# matrix_led_shield_schematic.net
KiCad netlist of a schematic drawn in EAGLE
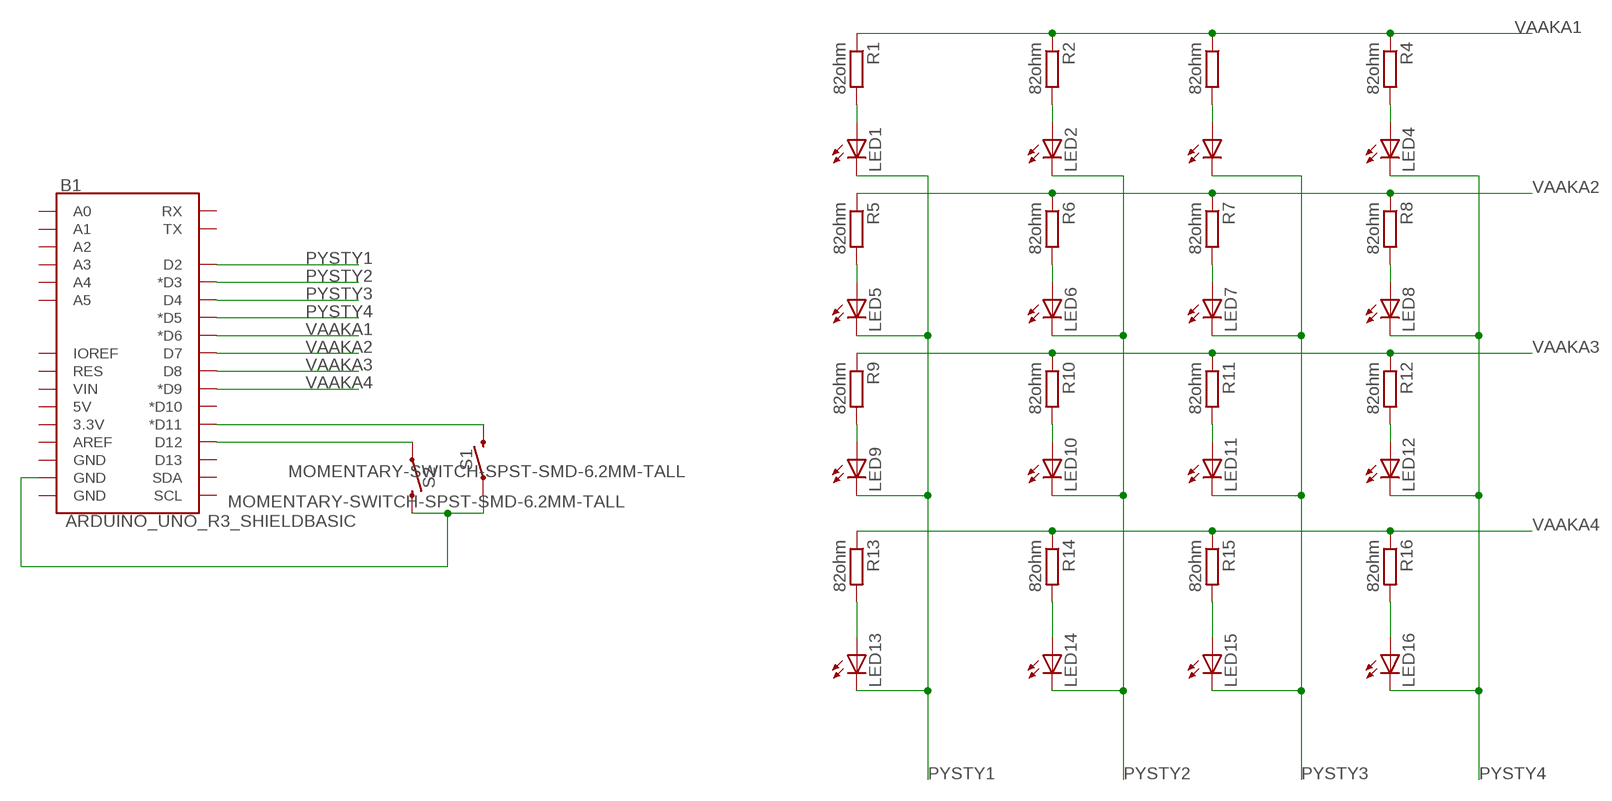
[diagram p0: schematic, sheet 1]

(export (version "E")
  (design (tool "Eeschema 10.0.6"))
  (components
    (comp (ref "B1")
      (value "ARDUINO_UNO_R3_SHIELDBASIC")
      (footprint "eagle-import:UNO_R3_SHIELD")
      (libsource (lib "eagle-import") (part "ARDUINO_UNO_R3_SHIELDBASIC"))
    )
    (comp (ref "LED1")
      (value "LG_T679-E1F1-1")
      (footprint "eagle-import:PLCC2")
      (libsource (lib "eagle-import") (part "_T679-?-1E1F1LG"))
    )
    (comp (ref "LED2")
      (value "LG_T679-E1F1-1")
      (footprint "eagle-import:PLCC2")
      (libsource (lib "eagle-import") (part "_T679-?-1E1F1LG"))
    )
    (comp (ref "LED3")
      (value "LG_T679-E1F1-1")
      (footprint "eagle-import:PLCC2")
      (libsource (lib "eagle-import") (part "_T679-?-1E1F1LG"))
    )
    (comp (ref "LED4")
      (value "LG_T679-E1F1-1")
      (footprint "eagle-import:PLCC2")
      (libsource (lib "eagle-import") (part "_T679-?-1E1F1LG"))
    )
    (comp (ref "LED5")
      (value "LG_T679-E1F1-1")
      (footprint "eagle-import:PLCC2")
      (libsource (lib "eagle-import") (part "_T679-?-1E1F1LG"))
    )
    (comp (ref "LED6")
      (value "LG_T679-E1F1-1")
      (footprint "eagle-import:PLCC2")
      (libsource (lib "eagle-import") (part "_T679-?-1E1F1LG"))
    )
    (comp (ref "LED7")
      (value "LG_T679-E1F1-1")
      (footprint "eagle-import:PLCC2")
      (libsource (lib "eagle-import") (part "_T679-?-1E1F1LG"))
    )
    (comp (ref "LED8")
      (value "LG_T679-E1F1-1")
      (footprint "eagle-import:PLCC2")
      (libsource (lib "eagle-import") (part "_T679-?-1E1F1LG"))
    )
    (comp (ref "LED9")
      (value "LG_T679-E1F1-1")
      (footprint "eagle-import:PLCC2")
      (libsource (lib "eagle-import") (part "_T679-?-1E1F1LG"))
    )
    (comp (ref "LED10")
      (value "LG_T679-E1F1-1")
      (footprint "eagle-import:PLCC2")
      (libsource (lib "eagle-import") (part "_T679-?-1E1F1LG"))
    )
    (comp (ref "LED11")
      (value "LG_T679-E1F1-1")
      (footprint "eagle-import:PLCC2")
      (libsource (lib "eagle-import") (part "_T679-?-1E1F1LG"))
    )
    (comp (ref "LED12")
      (value "LG_T679-E1F1-1")
      (footprint "eagle-import:PLCC2")
      (libsource (lib "eagle-import") (part "_T679-?-1E1F1LG"))
    )
    (comp (ref "LED13")
      (value "LG_T679-E1F1-1")
      (footprint "eagle-import:PLCC2")
      (libsource (lib "eagle-import") (part "_T679-?-1E1F1LG"))
    )
    (comp (ref "LED14")
      (value "LG_T679-E1F1-1")
      (footprint "eagle-import:PLCC2")
      (libsource (lib "eagle-import") (part "_T679-?-1E1F1LG"))
    )
    (comp (ref "LED15")
      (value "LG_T679-E1F1-1")
      (footprint "eagle-import:PLCC2")
      (libsource (lib "eagle-import") (part "_T679-?-1E1F1LG"))
    )
    (comp (ref "LED16")
      (value "LG_T679-E1F1-1")
      (footprint "eagle-import:PLCC2")
      (libsource (lib "eagle-import") (part "_T679-?-1E1F1LG"))
    )
    (comp (ref "R1")
      (value "82ohm")
      (footprint "eagle-import:M0805")
      (libsource (lib "eagle-import") (part "R-EU_M0805"))
    )
    (comp (ref "R2")
      (value "82ohm")
      (footprint "eagle-import:M0805")
      (libsource (lib "eagle-import") (part "R-EU_M0805"))
    )
    (comp (ref "R3")
      (value "82ohm")
      (footprint "eagle-import:M0805")
      (libsource (lib "eagle-import") (part "R-EU_M0805"))
    )
    (comp (ref "R4")
      (value "82ohm")
      (footprint "eagle-import:M0805")
      (libsource (lib "eagle-import") (part "R-EU_M0805"))
    )
    (comp (ref "R5")
      (value "82ohm")
      (footprint "eagle-import:M0805")
      (libsource (lib "eagle-import") (part "R-EU_M0805"))
    )
    (comp (ref "R6")
      (value "82ohm")
      (footprint "eagle-import:M0805")
      (libsource (lib "eagle-import") (part "R-EU_M0805"))
    )
    (comp (ref "R7")
      (value "82ohm")
      (footprint "eagle-import:M0805")
      (libsource (lib "eagle-import") (part "R-EU_M0805"))
    )
    (comp (ref "R8")
      (value "82ohm")
      (footprint "eagle-import:M0805")
      (libsource (lib "eagle-import") (part "R-EU_M0805"))
    )
    (comp (ref "R9")
      (value "82ohm")
      (footprint "eagle-import:M0805")
      (libsource (lib "eagle-import") (part "R-EU_M0805"))
    )
    (comp (ref "R10")
      (value "82ohm")
      (footprint "eagle-import:M0805")
      (libsource (lib "eagle-import") (part "R-EU_M0805"))
    )
    (comp (ref "R11")
      (value "82ohm")
      (footprint "eagle-import:M0805")
      (libsource (lib "eagle-import") (part "R-EU_M0805"))
    )
    (comp (ref "R12")
      (value "82ohm")
      (footprint "eagle-import:M0805")
      (libsource (lib "eagle-import") (part "R-EU_M0805"))
    )
    (comp (ref "R13")
      (value "82ohm")
      (footprint "eagle-import:M0805")
      (libsource (lib "eagle-import") (part "R-EU_M0805"))
    )
    (comp (ref "R14")
      (value "82ohm")
      (footprint "eagle-import:M0805")
      (libsource (lib "eagle-import") (part "R-EU_M0805"))
    )
    (comp (ref "R15")
      (value "82ohm")
      (footprint "eagle-import:M0805")
      (libsource (lib "eagle-import") (part "R-EU_M0805"))
    )
    (comp (ref "R16")
      (value "82ohm")
      (footprint "eagle-import:M0805")
      (libsource (lib "eagle-import") (part "R-EU_M0805"))
    )
    (comp (ref "S1")
      (value "MOMENTARY-SWITCH-SPST-SMD-6.2MM-TALL")
      (footprint "eagle-import:TACTILE_SWITCH_SMD_6.2MM_TALL")
      (libsource (lib "eagle-import") (part "MOMENTARY-SWITCH-SPST-SMD-6.2MM-TALL"))
    )
    (comp (ref "S2")
      (value "MOMENTARY-SWITCH-SPST-SMD-6.2MM-TALL")
      (footprint "eagle-import:TACTILE_SWITCH_SMD_6.2MM_TALL")
      (libsource (lib "eagle-import") (part "MOMENTARY-SWITCH-SPST-SMD-6.2MM-TALL"))
    )
  )
  (nets
    (net (code "1") (name "/PYSTY1") (class "Default")
      (node (ref "B1") (pin "D2") (pinfunction "D2_D2") (pintype "bidirectional"))
      (node (ref "LED1") (pin "C") (pinfunction "C_C") (pintype "passive"))
      (node (ref "LED13") (pin "C") (pinfunction "C_C") (pintype "passive"))
      (node (ref "LED5") (pin "C") (pinfunction "C_C") (pintype "passive"))
      (node (ref "LED9") (pin "C") (pinfunction "C_C") (pintype "passive"))
    )
    (net (code "2") (name "/PYSTY2") (class "Default")
      (node (ref "B1") (pin "D3") (pinfunction "*D3_D3") (pintype "bidirectional"))
      (node (ref "LED10") (pin "C") (pinfunction "C_C") (pintype "passive"))
      (node (ref "LED14") (pin "C") (pinfunction "C_C") (pintype "passive"))
      (node (ref "LED2") (pin "C") (pinfunction "C_C") (pintype "passive"))
      (node (ref "LED6") (pin "C") (pinfunction "C_C") (pintype "passive"))
    )
    (net (code "3") (name "/PYSTY3") (class "Default")
      (node (ref "B1") (pin "D4") (pinfunction "D4_D4") (pintype "bidirectional"))
      (node (ref "LED11") (pin "C") (pinfunction "C_C") (pintype "passive"))
      (node (ref "LED15") (pin "C") (pinfunction "C_C") (pintype "passive"))
      (node (ref "LED3") (pin "C") (pinfunction "C_C") (pintype "passive"))
      (node (ref "LED7") (pin "C") (pinfunction "C_C") (pintype "passive"))
    )
    (net (code "4") (name "/PYSTY4") (class "Default")
      (node (ref "B1") (pin "D5") (pinfunction "*D5_D5") (pintype "bidirectional"))
      (node (ref "LED12") (pin "C") (pinfunction "C_C") (pintype "passive"))
      (node (ref "LED16") (pin "C") (pinfunction "C_C") (pintype "passive"))
      (node (ref "LED4") (pin "C") (pinfunction "C_C") (pintype "passive"))
      (node (ref "LED8") (pin "C") (pinfunction "C_C") (pintype "passive"))
    )
    (net (code "5") (name "/VAAKA1") (class "Default")
      (node (ref "B1") (pin "D6") (pinfunction "*D6_D6") (pintype "bidirectional"))
      (node (ref "R1") (pin "1") (pinfunction "1_1") (pintype "passive"))
      (node (ref "R2") (pin "1") (pinfunction "1_1") (pintype "passive"))
      (node (ref "R3") (pin "1") (pinfunction "1_1") (pintype "passive"))
      (node (ref "R4") (pin "1") (pinfunction "1_1") (pintype "passive"))
    )
    (net (code "6") (name "/VAAKA2") (class "Default")
      (node (ref "B1") (pin "D7") (pinfunction "D7_D7") (pintype "bidirectional"))
      (node (ref "R5") (pin "1") (pinfunction "1_1") (pintype "passive"))
      (node (ref "R6") (pin "1") (pinfunction "1_1") (pintype "passive"))
      (node (ref "R7") (pin "1") (pinfunction "1_1") (pintype "passive"))
      (node (ref "R8") (pin "1") (pinfunction "1_1") (pintype "passive"))
    )
    (net (code "7") (name "/VAAKA3") (class "Default")
      (node (ref "B1") (pin "D8") (pinfunction "D8_D8") (pintype "bidirectional"))
      (node (ref "R10") (pin "1") (pinfunction "1_1") (pintype "passive"))
      (node (ref "R11") (pin "1") (pinfunction "1_1") (pintype "passive"))
      (node (ref "R12") (pin "1") (pinfunction "1_1") (pintype "passive"))
      (node (ref "R9") (pin "1") (pinfunction "1_1") (pintype "passive"))
    )
    (net (code "8") (name "/VAAKA4") (class "Default")
      (node (ref "B1") (pin "D9") (pinfunction "*D9_D9") (pintype "bidirectional"))
      (node (ref "R13") (pin "1") (pinfunction "1_1") (pintype "passive"))
      (node (ref "R14") (pin "1") (pinfunction "1_1") (pintype "passive"))
      (node (ref "R15") (pin "1") (pinfunction "1_1") (pintype "passive"))
      (node (ref "R16") (pin "1") (pinfunction "1_1") (pintype "passive"))
    )
    (net (code "9") (name "Net-(B1-*D11)") (class "Default")
      (node (ref "B1") (pin "D11") (pinfunction "*D11_D11") (pintype "bidirectional"))
      (node (ref "S1") (pin "B2") (pinfunction "2_B2") (pintype "passive"))
    )
    (net (code "10") (name "Net-(LED1-PadA)") (class "Default")
      (node (ref "LED1") (pin "A") (pinfunction "A_A") (pintype "passive"))
      (node (ref "R1") (pin "2") (pinfunction "2_2") (pintype "passive"))
    )
    (net (code "11") (name "Net-(LED2-PadA)") (class "Default")
      (node (ref "LED2") (pin "A") (pinfunction "A_A") (pintype "passive"))
      (node (ref "R2") (pin "2") (pinfunction "2_2") (pintype "passive"))
    )
    (net (code "12") (name "Net-(LED3-PadA)") (class "Default")
      (node (ref "LED3") (pin "A") (pinfunction "A_A") (pintype "passive"))
      (node (ref "R3") (pin "2") (pinfunction "2_2") (pintype "passive"))
    )
    (net (code "13") (name "Net-(LED4-PadA)") (class "Default")
      (node (ref "LED4") (pin "A") (pinfunction "A_A") (pintype "passive"))
      (node (ref "R4") (pin "2") (pinfunction "2_2") (pintype "passive"))
    )
    (net (code "14") (name "Net-(LED5-PadA)") (class "Default")
      (node (ref "LED5") (pin "A") (pinfunction "A_A") (pintype "passive"))
      (node (ref "R5") (pin "2") (pinfunction "2_2") (pintype "passive"))
    )
    (net (code "15") (name "Net-(LED6-PadA)") (class "Default")
      (node (ref "LED6") (pin "A") (pinfunction "A_A") (pintype "passive"))
      (node (ref "R6") (pin "2") (pinfunction "2_2") (pintype "passive"))
    )
    (net (code "16") (name "Net-(LED7-PadA)") (class "Default")
      (node (ref "LED7") (pin "A") (pinfunction "A_A") (pintype "passive"))
      (node (ref "R7") (pin "2") (pinfunction "2_2") (pintype "passive"))
    )
    (net (code "17") (name "Net-(LED8-PadA)") (class "Default")
      (node (ref "LED8") (pin "A") (pinfunction "A_A") (pintype "passive"))
      (node (ref "R8") (pin "2") (pinfunction "2_2") (pintype "passive"))
    )
    (net (code "18") (name "Net-(LED9-PadA)") (class "Default")
      (node (ref "LED9") (pin "A") (pinfunction "A_A") (pintype "passive"))
      (node (ref "R9") (pin "2") (pinfunction "2_2") (pintype "passive"))
    )
    (net (code "19") (name "Net-(LED10-PadA)") (class "Default")
      (node (ref "LED10") (pin "A") (pinfunction "A_A") (pintype "passive"))
      (node (ref "R10") (pin "2") (pinfunction "2_2") (pintype "passive"))
    )
    (net (code "20") (name "Net-(LED11-PadA)") (class "Default")
      (node (ref "LED11") (pin "A") (pinfunction "A_A") (pintype "passive"))
      (node (ref "R11") (pin "2") (pinfunction "2_2") (pintype "passive"))
    )
    (net (code "21") (name "Net-(LED12-PadA)") (class "Default")
      (node (ref "LED12") (pin "A") (pinfunction "A_A") (pintype "passive"))
      (node (ref "R12") (pin "2") (pinfunction "2_2") (pintype "passive"))
    )
    (net (code "22") (name "Net-(LED13-PadA)") (class "Default")
      (node (ref "LED13") (pin "A") (pinfunction "A_A") (pintype "passive"))
      (node (ref "R13") (pin "2") (pinfunction "2_2") (pintype "passive"))
    )
    (net (code "23") (name "Net-(LED14-PadA)") (class "Default")
      (node (ref "LED14") (pin "A") (pinfunction "A_A") (pintype "passive"))
      (node (ref "R14") (pin "2") (pinfunction "2_2") (pintype "passive"))
    )
    (net (code "24") (name "Net-(LED15-PadA)") (class "Default")
      (node (ref "LED15") (pin "A") (pinfunction "A_A") (pintype "passive"))
      (node (ref "R15") (pin "2") (pinfunction "2_2") (pintype "passive"))
    )
    (net (code "25") (name "Net-(LED16-PadA)") (class "Default")
      (node (ref "LED16") (pin "A") (pinfunction "A_A") (pintype "passive"))
      (node (ref "R16") (pin "2") (pinfunction "2_2") (pintype "passive"))
    )
    (net (code "26") (name "Net-(S1-1)") (class "Default")
      (node (ref "B1") (pin "GND@1") (pinfunction "GND_GND@1") (pintype "bidirectional"))
      (node (ref "S1") (pin "A2") (pinfunction "1_A2") (pintype "passive"))
      (node (ref "S2") (pin "B2") (pinfunction "2_B2") (pintype "passive"))
    )
    (net (code "27") (name "Net-(S2-1)") (class "Default")
      (node (ref "B1") (pin "D12") (pinfunction "D12_D12") (pintype "bidirectional"))
      (node (ref "S2") (pin "A2") (pinfunction "1_A2") (pintype "passive"))
    )
    (net (code "28") (name "unconnected-(B1-*D10-PadD10)") (class "Default")
      (node (ref "B1") (pin "D10") (pinfunction "*D10_D10") (pintype "bidirectional"))
    )
    (net (code "29") (name "unconnected-(B1-GND-PadGND@0)") (class "Default")
      (node (ref "B1") (pin "GND@0") (pinfunction "GND_GND@0") (pintype "bidirectional"))
    )
    (net (code "30") (name "unconnected-(B1-GND-PadGND@2)") (class "Default")
      (node (ref "B1") (pin "GND@2") (pinfunction "GND_GND@2") (pintype "bidirectional"))
    )
    (net (code "31") (name "unconnected-(B1-Pad3.3V)") (class "Default")
      (node (ref "B1") (pin "3.3V") (pinfunction "3.3V_3.3V") (pintype "bidirectional"))
    )
    (net (code "32") (name "unconnected-(B1-Pad5V)") (class "Default")
      (node (ref "B1") (pin "5V") (pinfunction "5V_5V") (pintype "bidirectional"))
    )
    (net (code "33") (name "unconnected-(B1-PadA0)") (class "Default")
      (node (ref "B1") (pin "A0") (pinfunction "A0_A0") (pintype "bidirectional"))
    )
    (net (code "34") (name "unconnected-(B1-PadA1)") (class "Default")
      (node (ref "B1") (pin "A1") (pinfunction "A1_A1") (pintype "bidirectional"))
    )
    (net (code "35") (name "unconnected-(B1-PadA2)") (class "Default")
      (node (ref "B1") (pin "A2") (pinfunction "A2_A2") (pintype "bidirectional"))
    )
    (net (code "36") (name "unconnected-(B1-PadA3)") (class "Default")
      (node (ref "B1") (pin "A3") (pinfunction "A3_A3") (pintype "bidirectional"))
    )
    (net (code "37") (name "unconnected-(B1-PadA4)") (class "Default")
      (node (ref "B1") (pin "A4") (pinfunction "A4_A4") (pintype "bidirectional"))
    )
    (net (code "38") (name "unconnected-(B1-PadA5)") (class "Default")
      (node (ref "B1") (pin "A5") (pinfunction "A5_A5") (pintype "bidirectional"))
    )
    (net (code "39") (name "unconnected-(B1-PadAREF)") (class "Default")
      (node (ref "B1") (pin "AREF") (pinfunction "AREF_AREF") (pintype "bidirectional"))
    )
    (net (code "40") (name "unconnected-(B1-PadD13)") (class "Default")
      (node (ref "B1") (pin "D13") (pinfunction "D13_D13") (pintype "bidirectional"))
    )
    (net (code "41") (name "unconnected-(B1-PadIOREF)") (class "Default")
      (node (ref "B1") (pin "IOREF") (pinfunction "IOREF_IOREF") (pintype "bidirectional"))
    )
    (net (code "42") (name "unconnected-(B1-PadRES)") (class "Default")
      (node (ref "B1") (pin "RES") (pinfunction "RES_RES") (pintype "bidirectional"))
    )
    (net (code "43") (name "unconnected-(B1-PadRX)") (class "Default")
      (node (ref "B1") (pin "RX") (pinfunction "RX_RX") (pintype "bidirectional"))
    )
    (net (code "44") (name "unconnected-(B1-PadSCL)") (class "Default")
      (node (ref "B1") (pin "SCL") (pinfunction "SCL_SCL") (pintype "bidirectional"))
    )
    (net (code "45") (name "unconnected-(B1-PadSDA)") (class "Default")
      (node (ref "B1") (pin "SDA") (pinfunction "SDA_SDA") (pintype "bidirectional"))
    )
    (net (code "46") (name "unconnected-(B1-PadTX)") (class "Default")
      (node (ref "B1") (pin "TX") (pinfunction "TX_TX") (pintype "bidirectional"))
    )
    (net (code "47") (name "unconnected-(B1-PadVIN)") (class "Default")
      (node (ref "B1") (pin "VIN") (pinfunction "VIN_VIN") (pintype "bidirectional"))
    )
  )
)
